# ADC.net
KiCad netlist of a schematic drawn in Altium Designer
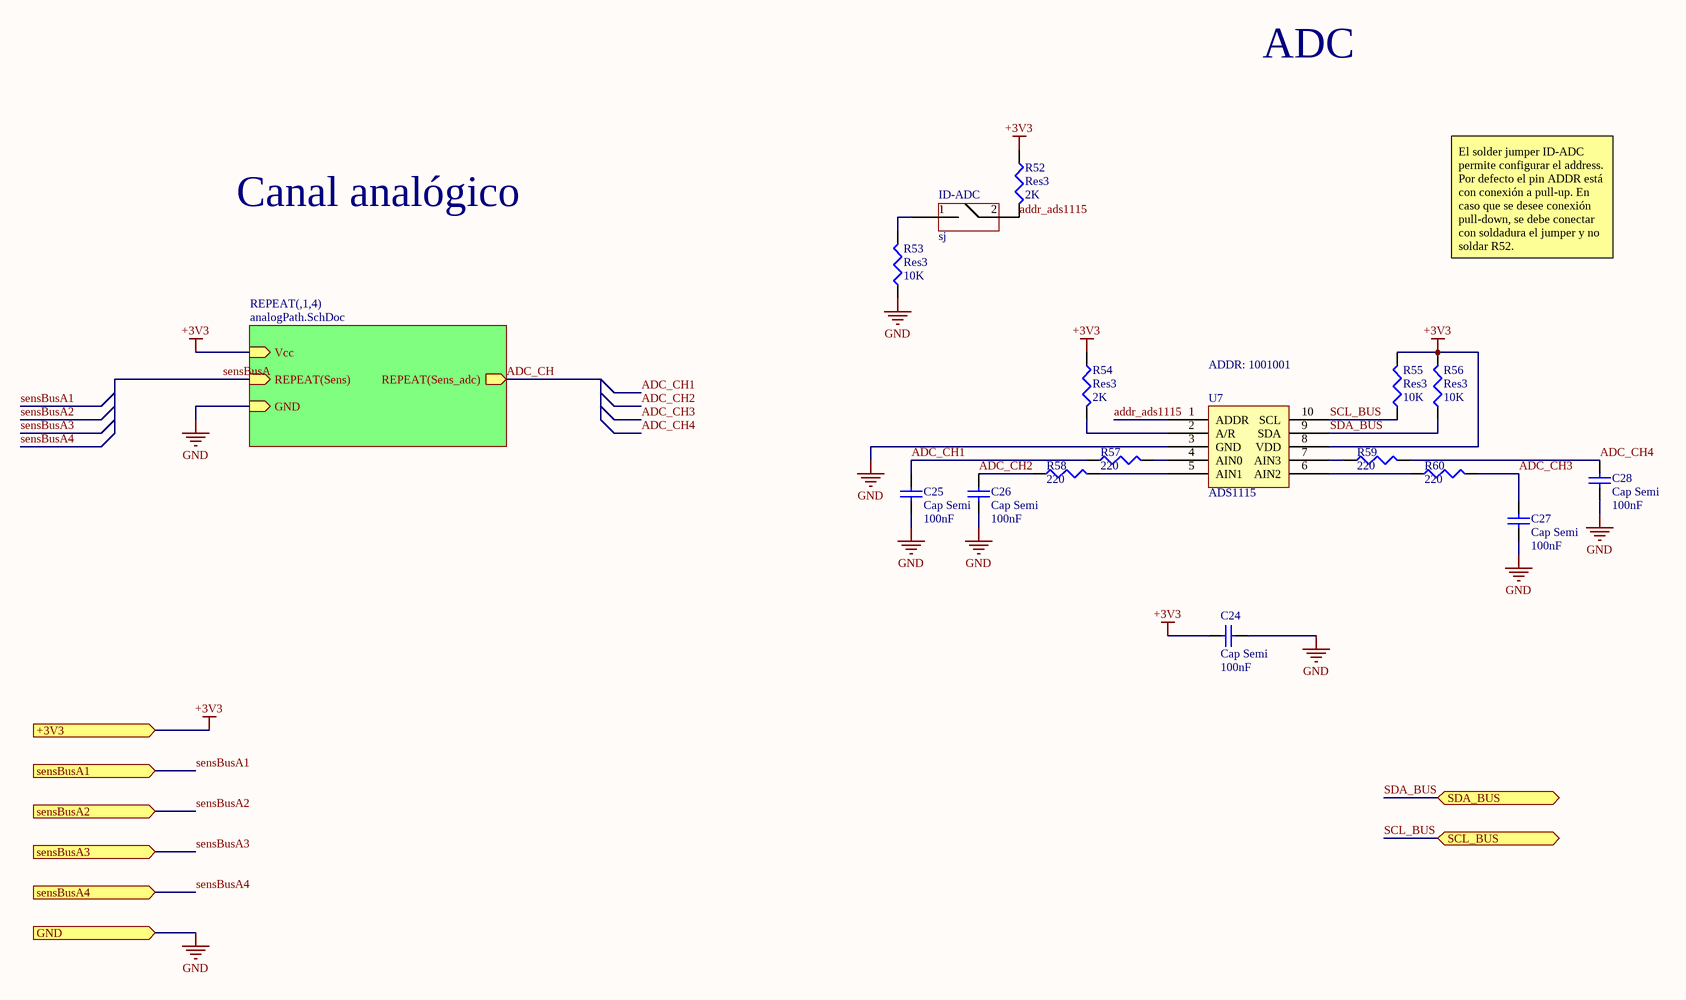
[diagram p0: ADC.SchDoc]

(export (version "E")
  (design (tool "Eeschema 10.0.6"))
  (components
    (comp (ref "C24")
      (value "Cap Semi")
      (footprint "1608[0603]")
      (description "Capacitor (Semiconductor SIM Model)")
      (fields
        (field (name "ALTIUM_VALUE") "100nF")
        (field (name "MANUFACTURER") "Taiyo Yuden")
        (field (name "MANUFACTURER PART NUMBER") "UMK107B104KAHT")
        (field (name "PUBLISHER") "Altium Limited")
      )
      (libsource (lib "Miscellaneous Devices") (part "Cap Semi"))
    )
    (comp (ref "C25")
      (value "Cap Semi")
      (footprint "1608[0603]")
      (description "Capacitor (Semiconductor SIM Model)")
      (fields
        (field (name "ALTIUM_VALUE") "100nF")
        (field (name "MANUFACTURER PART NUMBER") "UMK107B104KAHT")
        (field (name "MANUFACTURER") "Taiyo Yuden")
        (field (name "PUBLISHER") "Altium Limited")
      )
      (libsource (lib "Miscellaneous Devices") (part "Cap Semi"))
    )
    (comp (ref "C26")
      (value "Cap Semi")
      (footprint "1608[0603]")
      (description "Capacitor (Semiconductor SIM Model)")
      (fields
        (field (name "ALTIUM_VALUE") "100nF")
        (field (name "MANUFACTURER") "Taiyo Yuden")
        (field (name "MANUFACTURER PART NUMBER") "UMK107B104KAHT")
        (field (name "PUBLISHER") "Altium Limited")
      )
      (libsource (lib "Miscellaneous Devices") (part "Cap Semi"))
    )
    (comp (ref "C27")
      (value "Cap Semi")
      (footprint "1608[0603]")
      (description "Capacitor (Semiconductor SIM Model)")
      (fields
        (field (name "ALTIUM_VALUE") "100nF")
        (field (name "MANUFACTURER PART NUMBER") "UMK107B104KAHT")
        (field (name "MANUFACTURER") "Taiyo Yuden")
        (field (name "PUBLISHER") "Altium Limited")
      )
      (libsource (lib "Miscellaneous Devices") (part "Cap Semi"))
    )
    (comp (ref "C28")
      (value "Cap Semi")
      (footprint "1608[0603]")
      (description "Capacitor (Semiconductor SIM Model)")
      (fields
        (field (name "ALTIUM_VALUE") "100nF")
        (field (name "MANUFACTURER") "Taiyo Yuden")
        (field (name "MANUFACTURER PART NUMBER") "UMK107B104KAHT")
        (field (name "PUBLISHER") "Altium Limited")
      )
      (libsource (lib "Miscellaneous Devices") (part "Cap Semi"))
    )
    (comp (ref "ID-ADC")
      (value "sj")
      (footprint "SJ2")
      (description "solder jumper generic")
      (libsource (lib "IoWLabs") (part "Jumper"))
    )
    (comp (ref "R52")
      (value "Res3")
      (footprint "J1-0603")
      (description "Resistor")
      (fields
        (field (name "ALTIUM_VALUE") "2K")
        (field (name "MANUFACTURER") "YAGEO")
        (field (name "MANUFACTURER PART NUMBER") "RC0603FR-072KL")
        (field (name "PUBLISHER") "Altium Limited")
      )
      (libsource (lib "Miscellaneous Devices") (part "Res3"))
    )
    (comp (ref "R53")
      (value "Res3")
      (footprint "J1-0603")
      (description "Resistor")
      (fields
        (field (name "ALTIUM_VALUE") "10K")
        (field (name "MANUFACTURER") "PANASONIC")
        (field (name "MANUFACTURER PART NUMBER") "ERJPA3F1002V")
        (field (name "PUBLISHER") "Altium Limited")
      )
      (libsource (lib "Miscellaneous Devices") (part "Res3"))
    )
    (comp (ref "R54")
      (value "Res3")
      (footprint "J1-0603")
      (description "Resistor")
      (fields
        (field (name "ALTIUM_VALUE") "2K")
        (field (name "MANUFACTURER") "YAGEO")
        (field (name "MANUFACTURER PART NUMBER") "RC0603FR-072KL")
        (field (name "PUBLISHER") "Altium Limited")
      )
      (libsource (lib "Miscellaneous Devices") (part "Res3"))
    )
    (comp (ref "R55")
      (value "Res3")
      (footprint "J1-0603")
      (description "Resistor")
      (fields
        (field (name "ALTIUM_VALUE") "10K")
        (field (name "MANUFACTURER") "PANASONIC")
        (field (name "MANUFACTURER PART NUMBER") "ERJPA3F1002V")
        (field (name "PUBLISHER") "Altium Limited")
      )
      (libsource (lib "Miscellaneous Devices") (part "Res3"))
    )
    (comp (ref "R56")
      (value "Res3")
      (footprint "J1-0603")
      (description "Resistor")
      (fields
        (field (name "ALTIUM_VALUE") "10K")
        (field (name "MANUFACTURER") "PANASONIC")
        (field (name "MANUFACTURER PART NUMBER") "ERJPA3F1002V")
        (field (name "PUBLISHER") "Altium Limited")
      )
      (libsource (lib "Miscellaneous Devices") (part "Res3"))
    )
    (comp (ref "R57")
      (value "220")
      (footprint "J1-0603")
      (description "Resistor")
      (fields
        (field (name "MANUFACTURER PART NUMBER") "RC0603FR-07220RL")
        (field (name "MANUFACTURER") "YAGEO")
        (field (name "PUBLISHER") "Altium Limited")
      )
      (libsource (lib "Miscellaneous Devices") (part "Res3"))
    )
    (comp (ref "R58")
      (value "220")
      (footprint "J1-0603")
      (description "Resistor")
      (fields
        (field (name "MANUFACTURER PART NUMBER") "RC0603FR-07220RL")
        (field (name "MANUFACTURER") "YAGEO")
        (field (name "PUBLISHER") "Altium Limited")
      )
      (libsource (lib "Miscellaneous Devices") (part "Res3"))
    )
    (comp (ref "R59")
      (value "220")
      (footprint "J1-0603")
      (description "Resistor")
      (fields
        (field (name "MANUFACTURER PART NUMBER") "RC0603FR-07220RL")
        (field (name "MANUFACTURER") "YAGEO")
        (field (name "PUBLISHER") "Altium Limited")
      )
      (libsource (lib "Miscellaneous Devices") (part "Res3"))
    )
    (comp (ref "R60")
      (value "220")
      (footprint "J1-0603")
      (description "Resistor")
      (fields
        (field (name "MANUFACTURER PART NUMBER") "RC0603FR-07220RL")
        (field (name "MANUFACTURER") "YAGEO")
        (field (name "PUBLISHER") "Altium Limited")
      )
      (libsource (lib "Miscellaneous Devices") (part "Res3"))
    )
    (comp (ref "U7")
      (value "ADS1115")
      (footprint "VSSOP - 10")
      (description "Analog To Digital Converters (ADCs) VSSOP-10 RoHS")
      (fields
        (field (name "MANUFACTURER PART NUMBER") "ADS1115QDGSRQ1")
        (field (name "MANUFACTURER") "Texas Instruments")
      )
      (libsource (lib "IoWLabs") (part "ADS1115QDGSRQ1"))
    )
  )
  (nets
    (net (code "1") (name "+3V3") (class "Default")
      (node (ref "C24") (pin "2") (pinfunction "2_2") (pintype "passive"))
      (node (ref "R52") (pin "1") (pinfunction "1_1") (pintype "passive"))
      (node (ref "R54") (pin "1") (pinfunction "1_1") (pintype "passive"))
      (node (ref "R55") (pin "2") (pinfunction "2_2") (pintype "passive"))
      (node (ref "R56") (pin "2") (pinfunction "2_2") (pintype "passive"))
      (node (ref "U7") (pin "8") (pinfunction "VDD_8") (pintype "passive"))
    )
    (net (code "3") (name "/ADC_CH1") (class "Default")
      (node (ref "C25") (pin "2") (pinfunction "2_2") (pintype "passive"))
      (node (ref "R57") (pin "1") (pinfunction "1_1") (pintype "passive"))
    )
    (net (code "4") (name "/ADC_CH2") (class "Default")
      (node (ref "C26") (pin "2") (pinfunction "2_2") (pintype "passive"))
      (node (ref "R58") (pin "1") (pinfunction "1_1") (pintype "passive"))
    )
    (net (code "5") (name "/ADC_CH3") (class "Default")
      (node (ref "C27") (pin "2") (pinfunction "2_2") (pintype "passive"))
      (node (ref "R60") (pin "2") (pinfunction "2_2") (pintype "passive"))
    )
    (net (code "6") (name "/ADC_CH4") (class "Default")
      (node (ref "C28") (pin "2") (pinfunction "2_2") (pintype "passive"))
      (node (ref "R59") (pin "2") (pinfunction "2_2") (pintype "passive"))
    )
    (net (code "7") (name "/SCL_BUS") (class "Default")
      (node (ref "R55") (pin "1") (pinfunction "1_1") (pintype "passive"))
      (node (ref "U7") (pin "10") (pinfunction "SCL_10") (pintype "passive"))
    )
    (net (code "8") (name "/SDA_BUS") (class "Default")
      (node (ref "R56") (pin "1") (pinfunction "1_1") (pintype "passive"))
      (node (ref "U7") (pin "9") (pinfunction "SDA_9") (pintype "passive"))
    )
    (net (code "9") (name "/addr_ads1115") (class "Default")
      (node (ref "ID-ADC") (pin "2") (pinfunction "2_2") (pintype "passive"))
      (node (ref "R52") (pin "2") (pinfunction "2_2") (pintype "passive"))
      (node (ref "U7") (pin "1") (pinfunction "ADDR_1") (pintype "passive"))
    )
    (net (code "15") (name "GND") (class "Default")
      (node (ref "C24") (pin "1") (pinfunction "1_1") (pintype "passive"))
      (node (ref "C25") (pin "1") (pinfunction "1_1") (pintype "passive"))
      (node (ref "C26") (pin "1") (pinfunction "1_1") (pintype "passive"))
      (node (ref "C27") (pin "1") (pinfunction "1_1") (pintype "passive"))
      (node (ref "C28") (pin "1") (pinfunction "1_1") (pintype "passive"))
      (node (ref "R53") (pin "1") (pinfunction "1_1") (pintype "passive"))
      (node (ref "U7") (pin "3") (pinfunction "GND_3") (pintype "passive"))
    )
    (net (code "16") (name "Net-(ID-ADC-Pad1)") (class "Default")
      (node (ref "ID-ADC") (pin "1") (pinfunction "1_1") (pintype "passive"))
      (node (ref "R53") (pin "2") (pinfunction "2_2") (pintype "passive"))
    )
    (net (code "17") (name "Net-(U7-AIN0)") (class "Default")
      (node (ref "R57") (pin "2") (pinfunction "2_2") (pintype "passive"))
      (node (ref "U7") (pin "4") (pinfunction "AIN0_4") (pintype "passive"))
    )
    (net (code "18") (name "Net-(U7-AIN1)") (class "Default")
      (node (ref "R58") (pin "2") (pinfunction "2_2") (pintype "passive"))
      (node (ref "U7") (pin "5") (pinfunction "AIN1_5") (pintype "passive"))
    )
    (net (code "19") (name "Net-(U7-AIN2)") (class "Default")
      (node (ref "R60") (pin "1") (pinfunction "1_1") (pintype "passive"))
      (node (ref "U7") (pin "6") (pinfunction "AIN2_6") (pintype "passive"))
    )
    (net (code "20") (name "Net-(U7-AIN3)") (class "Default")
      (node (ref "R59") (pin "1") (pinfunction "1_1") (pintype "passive"))
      (node (ref "U7") (pin "7") (pinfunction "AIN3_7") (pintype "passive"))
    )
    (net (code "21") (name "Net-(U7-A{slash}R)") (class "Default")
      (node (ref "R54") (pin "2") (pinfunction "2_2") (pintype "passive"))
      (node (ref "U7") (pin "2") (pinfunction "A/R_2") (pintype "passive"))
    )
  )
)
